# V-00684-00.net
KiCad netlist of a schematic drawn in EAGLE
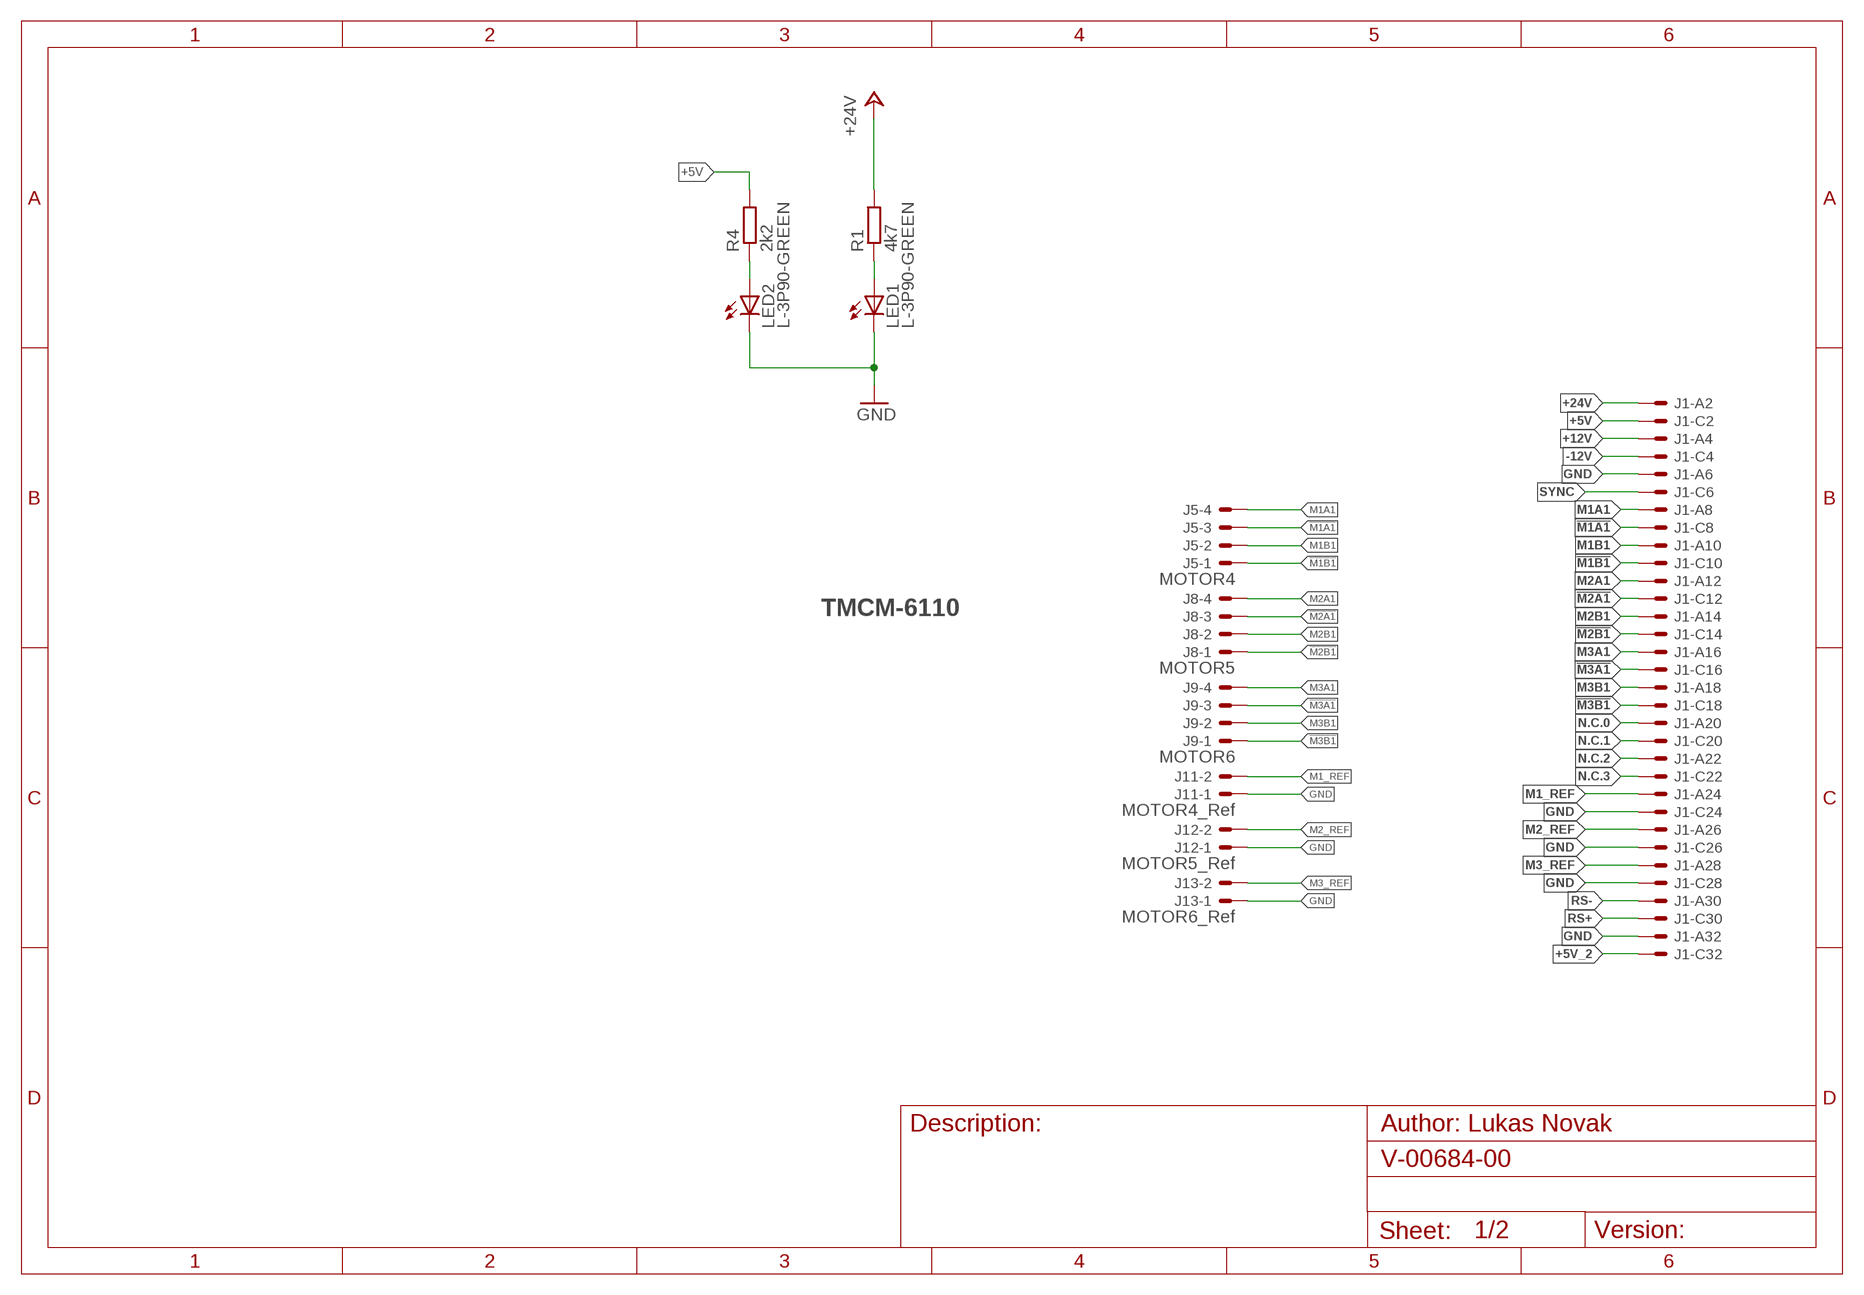
[diagram p0: schematic, sheet 1]

(export (version "E")
  (design (tool "Eeschema 10.0.6"))
  (components
    (comp (ref "J1")
      (value "VG32SP")
      (footprint "eagle-import:VG32P")
      (libsource (lib "eagle-import") (part "VG32SP"))
    )
    (comp (ref "J5")
      (value "MOTOR4")
      (footprint "eagle-import:7395-04")
      (libsource (lib "eagle-import") (part "22-?-0405-7048"))
    )
    (comp (ref "J8")
      (value "MOTOR5")
      (footprint "eagle-import:7395-04")
      (libsource (lib "eagle-import") (part "22-?-0405-7048"))
    )
    (comp (ref "J9")
      (value "MOTOR6")
      (footprint "eagle-import:7395-04")
      (libsource (lib "eagle-import") (part "22-?-0405-7048"))
    )
    (comp (ref "J11")
      (value "MOTOR4_Ref")
      (footprint "eagle-import:7395-02")
      (libsource (lib "eagle-import") (part "22-?-0205-7028"))
    )
    (comp (ref "J12")
      (value "MOTOR5_Ref")
      (footprint "eagle-import:7395-02")
      (libsource (lib "eagle-import") (part "22-?-0205-7028"))
    )
    (comp (ref "J13")
      (value "MOTOR6_Ref")
      (footprint "eagle-import:7395-02")
      (libsource (lib "eagle-import") (part "22-?-0205-7028"))
    )
    (comp (ref "LED1")
      (value "L-3P90-GREEN")
      (footprint "eagle-import:L-3P90")
      (libsource (lib "eagle-import") (part "L-3P90-GREEN"))
    )
    (comp (ref "LED2")
      (value "L-3P90-GREEN")
      (footprint "eagle-import:L-3P90")
      (libsource (lib "eagle-import") (part "L-3P90-GREEN"))
    )
    (comp (ref "R1")
      (value "4k7")
      (footprint "eagle-import:R1206")
      (libsource (lib "eagle-import") (part "R-EU_R1206"))
    )
    (comp (ref "R4")
      (value "2k2")
      (footprint "eagle-import:R1206")
      (libsource (lib "eagle-import") (part "R-EU_R1206"))
    )
  )
  (nets
    (net (code "1") (name "+5V") (class "Default")
      (node (ref "J1") (pin "C2") (pinfunction "MS_C2") (pintype "passive"))
      (node (ref "R4") (pin "2") (pinfunction "2_2") (pintype "passive"))
    )
    (net (code "2") (name "+5V_2") (class "Default")
      (node (ref "J1") (pin "C32") (pinfunction "MSV_C32") (pintype "passive"))
    )
    (net (code "3") (name "+12V") (class "Default")
      (node (ref "J1") (pin "A4") (pinfunction "MS_A4") (pintype "passive"))
    )
    (net (code "4") (name "+24V") (class "Default")
      (node (ref "J1") (pin "A2") (pinfunction "MS_A2") (pintype "passive"))
      (node (ref "R1") (pin "2") (pinfunction "2_2") (pintype "passive"))
    )
    (net (code "5") (name "-12V") (class "Default")
      (node (ref "J1") (pin "C4") (pinfunction "MS_C4") (pintype "passive"))
    )
    (net (code "6") (name "GND") (class "Default")
      (node (ref "J1") (pin "A32") (pinfunction "MS_A32") (pintype "passive"))
      (node (ref "J1") (pin "A6") (pinfunction "MS_A6") (pintype "passive"))
      (node (ref "J1") (pin "C24") (pinfunction "MS_C24") (pintype "passive"))
      (node (ref "J1") (pin "C26") (pinfunction "MS_C26") (pintype "passive"))
      (node (ref "J1") (pin "C28") (pinfunction "MS_C28") (pintype "passive"))
      (node (ref "J11") (pin "1") (pinfunction "S_1") (pintype "passive"))
      (node (ref "J12") (pin "1") (pinfunction "S_1") (pintype "passive"))
      (node (ref "J13") (pin "1") (pinfunction "S_1") (pintype "passive"))
      (node (ref "LED1") (pin "K") (pinfunction "C_K") (pintype "passive"))
      (node (ref "LED2") (pin "K") (pinfunction "C_K") (pintype "passive"))
    )
    (net (code "7") (name "M1A1") (class "Default")
      (node (ref "J1") (pin "A8") (pinfunction "MS_A8") (pintype "passive"))
      (node (ref "J5") (pin "4") (pinfunction "S_4") (pintype "passive"))
    )
    (net (code "8") (name "M1B1") (class "Default")
      (node (ref "J1") (pin "A10") (pinfunction "MS_A10") (pintype "passive"))
      (node (ref "J5") (pin "2") (pinfunction "S_2") (pintype "passive"))
    )
    (net (code "9") (name "M1_REF") (class "Default")
      (node (ref "J1") (pin "A24") (pinfunction "MS_A24") (pintype "passive"))
      (node (ref "J11") (pin "2") (pinfunction "S_2") (pintype "passive"))
    )
    (net (code "10") (name "M2A1") (class "Default")
      (node (ref "J1") (pin "A12") (pinfunction "MS_A12") (pintype "passive"))
      (node (ref "J8") (pin "4") (pinfunction "S_4") (pintype "passive"))
    )
    (net (code "11") (name "M2B1") (class "Default")
      (node (ref "J1") (pin "A14") (pinfunction "MS_A14") (pintype "passive"))
      (node (ref "J8") (pin "2") (pinfunction "S_2") (pintype "passive"))
    )
    (net (code "12") (name "M2_REF") (class "Default")
      (node (ref "J1") (pin "A26") (pinfunction "MS_A26") (pintype "passive"))
      (node (ref "J12") (pin "2") (pinfunction "S_2") (pintype "passive"))
    )
    (net (code "13") (name "M3A1") (class "Default")
      (node (ref "J1") (pin "A16") (pinfunction "MS_A16") (pintype "passive"))
      (node (ref "J9") (pin "4") (pinfunction "S_4") (pintype "passive"))
    )
    (net (code "14") (name "M3B1") (class "Default")
      (node (ref "J1") (pin "A18") (pinfunction "MS_A18") (pintype "passive"))
      (node (ref "J9") (pin "2") (pinfunction "S_2") (pintype "passive"))
    )
    (net (code "15") (name "M3_REF") (class "Default")
      (node (ref "J1") (pin "A28") (pinfunction "MS_A28") (pintype "passive"))
      (node (ref "J13") (pin "2") (pinfunction "S_2") (pintype "passive"))
    )
    (net (code "16") (name "N.C.0") (class "Default")
      (node (ref "J1") (pin "A20") (pinfunction "MS_A20") (pintype "passive"))
    )
    (net (code "17") (name "N.C.1") (class "Default")
      (node (ref "J1") (pin "C20") (pinfunction "MS_C20") (pintype "passive"))
    )
    (net (code "18") (name "N.C.2") (class "Default")
      (node (ref "J1") (pin "A22") (pinfunction "MS_A22") (pintype "passive"))
    )
    (net (code "19") (name "N.C.3") (class "Default")
      (node (ref "J1") (pin "C22") (pinfunction "MS_C22") (pintype "passive"))
    )
    (net (code "20") (name "Net-(LED1-PadA)") (class "Default")
      (node (ref "LED1") (pin "A") (pinfunction "A_A") (pintype "passive"))
      (node (ref "R1") (pin "1") (pinfunction "1_1") (pintype "passive"))
    )
    (net (code "21") (name "Net-(LED2-PadA)") (class "Default")
      (node (ref "LED2") (pin "A") (pinfunction "A_A") (pintype "passive"))
      (node (ref "R4") (pin "1") (pinfunction "1_1") (pintype "passive"))
    )
    (net (code "22") (name "RS+") (class "Default")
      (node (ref "J1") (pin "C30") (pinfunction "MS_C30") (pintype "passive"))
    )
    (net (code "23") (name "RS-") (class "Default")
      (node (ref "J1") (pin "A30") (pinfunction "MS_A30") (pintype "passive"))
    )
    (net (code "24") (name "SYNC") (class "Default")
      (node (ref "J1") (pin "C6") (pinfunction "MS_C6") (pintype "passive"))
    )
    (net (code "25") (name "~{M1A1}") (class "Default")
      (node (ref "J1") (pin "C8") (pinfunction "MS_C8") (pintype "passive"))
      (node (ref "J5") (pin "3") (pinfunction "S_3") (pintype "passive"))
    )
    (net (code "26") (name "~{M1B1}") (class "Default")
      (node (ref "J1") (pin "C10") (pinfunction "MS_C10") (pintype "passive"))
      (node (ref "J5") (pin "1") (pinfunction "S_1") (pintype "passive"))
    )
    (net (code "27") (name "~{M2A1}") (class "Default")
      (node (ref "J1") (pin "C12") (pinfunction "MS_C12") (pintype "passive"))
      (node (ref "J8") (pin "3") (pinfunction "S_3") (pintype "passive"))
    )
    (net (code "28") (name "~{M2B1}") (class "Default")
      (node (ref "J1") (pin "C14") (pinfunction "MS_C14") (pintype "passive"))
      (node (ref "J8") (pin "1") (pinfunction "S_1") (pintype "passive"))
    )
    (net (code "29") (name "~{M3A1}") (class "Default")
      (node (ref "J1") (pin "C16") (pinfunction "MS_C16") (pintype "passive"))
      (node (ref "J9") (pin "3") (pinfunction "S_3") (pintype "passive"))
    )
    (net (code "30") (name "~{M3B1}") (class "Default")
      (node (ref "J1") (pin "C18") (pinfunction "MS_C18") (pintype "passive"))
      (node (ref "J9") (pin "1") (pinfunction "S_1") (pintype "passive"))
    )
  )
)
